# CAN0.net
KiCad netlist of a schematic drawn in Altium Designer
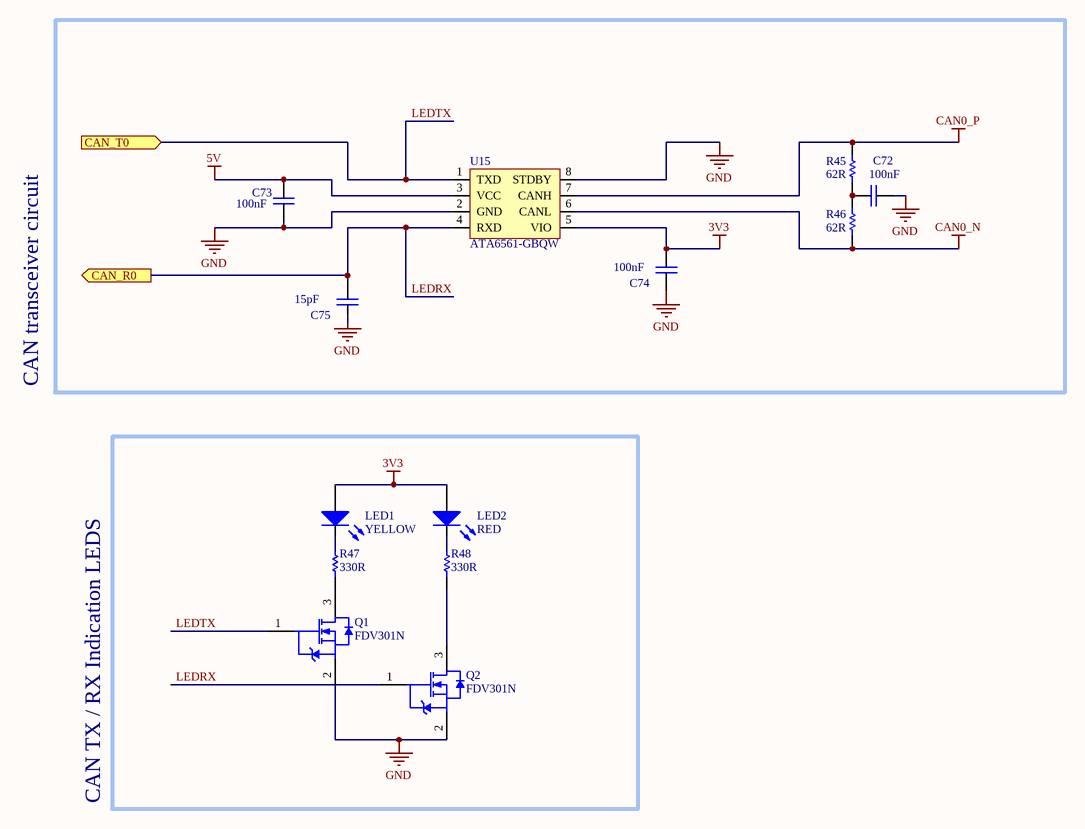
[diagram p0: CAN0.SchDoc]

(export (version "E")
  (design (tool "Eeschema 10.0.6"))
  (components
    (comp (ref "C72")
      (value "100nF")
      (footprint "C1206")
      (description "C1206")
      (fields (field (name "Comment") "C1206C106K3PACTU"))
      (libsource (lib "Passive components") (part "C1206C106K3PACTU"))
    )
    (comp (ref "C73")
      (value "100nF")
      (footprint "C1206")
      (description "C1206")
      (fields (field (name "Comment") "C1206C106K3PACTU"))
      (libsource (lib "Passive components") (part "C1206C106K3PACTU"))
    )
    (comp (ref "C74")
      (value "100nF")
      (footprint "C1206")
      (description "C1206")
      (fields (field (name "Comment") "C1206C106K3PACTU"))
      (libsource (lib "Passive components") (part "C1206C106K3PACTU"))
    )
    (comp (ref "C75")
      (value "15pF")
      (footprint "C1206")
      (description "C1206")
      (fields (field (name "Comment") "C1206C106K3PACTU"))
      (libsource (lib "Passive components") (part "C1206C106K3PACTU"))
    )
    (comp (ref "LED1")
      (value "YELLOW")
      (footprint "0603_A")
      (description "SMD mono-color Chip LED, WL-SMCW, Red")
      (fields (field (name "MANUFACTURER") "Wuerth Elektronik") (field (name "PARTNUMBER") "150060RS75000"))
      (libsource (lib "Altium Content Vault") (part "WE-LED_K1A2-2"))
    )
    (comp (ref "LED2")
      (value "RED")
      (footprint "0603_A")
      (description "SMD mono-color Chip LED, WL-SMCW, Red")
      (fields (field (name "MANUFACTURER") "Wuerth Elektronik") (field (name "PARTNUMBER") "150060RS75000"))
      (libsource (lib "Altium Content Vault") (part "WE-LED_K1A2-2"))
    )
    (comp (ref "Q1")
      (value "FDV301N")
      (footprint "FAIR-SOT23-3_V")
      (description "Digital FET, N-Channel, 0.35 W, 25 V, -55 to 150 degC, 3-Pin SOT23, RoHS, Tape and Reel")
      (fields (field (name "MANUFACTURER") "Fairchild"))
      (libsource (lib "Altium Content Vault") (part "NEMOS-GSD-3_D"))
    )
    (comp (ref "Q2")
      (value "FDV301N")
      (footprint "FAIR-SOT23-3_V")
      (description "Digital FET, N-Channel, 0.35 W, 25 V, -55 to 150 degC, 3-Pin SOT23, RoHS, Tape and Reel")
      (fields (field (name "MANUFACTURER") "Fairchild"))
      (libsource (lib "Altium Content Vault") (part "NEMOS-GSD-3_D"))
    )
    (comp (ref "R45")
      (value "62R")
      (footprint "RESC0603(1608)_L")
      (description "330R 0.1W 5% 0603 (1608 Metric)  SMD")
      (fields (field (name "TOLERANCE") "5 %") (field (name "POWER") "0.1 W"))
      (libsource (lib "Altium Content Vault") (part "RES"))
    )
    (comp (ref "R46")
      (value "62R")
      (footprint "RESC0603(1608)_L")
      (description "330R 0.1W 5% 0603 (1608 Metric)  SMD")
      (fields (field (name "TOLERANCE") "5 %") (field (name "POWER") "0.1 W"))
      (libsource (lib "Altium Content Vault") (part "RES"))
    )
    (comp (ref "R47")
      (value "330R")
      (footprint "RESC0603(1608)_L")
      (description "330R 0.1W 5% 0603 (1608 Metric)  SMD")
      (fields (field (name "TOLERANCE") "5 %") (field (name "POWER") "0.1 W"))
      (libsource (lib "Altium Content Vault") (part "RES"))
    )
    (comp (ref "R48")
      (value "330R")
      (footprint "RESC0603(1608)_L")
      (description "330R 0.1W 5% 0603 (1608 Metric)  SMD")
      (fields (field (name "TOLERANCE") "5 %") (field (name "POWER") "0.1 W"))
      (libsource (lib "Altium Content Vault") (part "RES"))
    )
    (comp (ref "U15")
      (value "ATA6561-GBQW")
      (footprint "LME49721MA/NOPB")
      (libsource (lib "IC") (part "ATA6561-GBQW"))
    )
  )
  (nets
    (net (code "1") (name "/LEDRX") (class "Default")
      (node (ref "C75") (pin "2") (pinfunction "2_2") (pintype "passive"))
      (node (ref "Q2") (pin "1") (pinfunction "G_1") (pintype "passive"))
      (node (ref "U15") (pin "4") (pinfunction "RXD_4") (pintype "passive"))
    )
    (net (code "2") (name "/LEDTX") (class "Default")
      (node (ref "Q1") (pin "1") (pinfunction "G_1") (pintype "passive"))
      (node (ref "U15") (pin "1") (pinfunction "TXD_1") (pintype "passive"))
    )
    (net (code "3") (name "3V3") (class "Default")
      (node (ref "C74") (pin "2") (pinfunction "2_2") (pintype "passive"))
      (node (ref "LED1") (pin "2") (pinfunction "A_2") (pintype "passive"))
      (node (ref "LED2") (pin "2") (pinfunction "A_2") (pintype "passive"))
      (node (ref "U15") (pin "5") (pinfunction "VIO_5") (pintype "passive"))
    )
    (net (code "4") (name "5V") (class "Default")
      (node (ref "C73") (pin "2") (pinfunction "2_2") (pintype "passive"))
      (node (ref "U15") (pin "3") (pinfunction "VCC_3") (pintype "passive"))
    )
    (net (code "5") (name "CAN0_N") (class "Default")
      (node (ref "R46") (pin "2") (pinfunction "2_2") (pintype "passive"))
      (node (ref "U15") (pin "6") (pinfunction "CANL_6") (pintype "passive"))
    )
    (net (code "6") (name "CAN0_P") (class "Default")
      (node (ref "R45") (pin "1") (pinfunction "1_1") (pintype "passive"))
      (node (ref "U15") (pin "7") (pinfunction "CANH_7") (pintype "passive"))
    )
    (net (code "7") (name "GND") (class "Default")
      (node (ref "C72") (pin "1") (pinfunction "1_1") (pintype "passive"))
      (node (ref "C73") (pin "1") (pinfunction "1_1") (pintype "passive"))
      (node (ref "C74") (pin "1") (pinfunction "1_1") (pintype "passive"))
      (node (ref "C75") (pin "1") (pinfunction "1_1") (pintype "passive"))
      (node (ref "Q1") (pin "2") (pinfunction "S_2") (pintype "passive"))
      (node (ref "Q2") (pin "2") (pinfunction "S_2") (pintype "passive"))
      (node (ref "U15") (pin "2") (pinfunction "GND_2") (pintype "passive"))
      (node (ref "U15") (pin "8") (pinfunction "STDBY_8") (pintype "passive"))
    )
    (net (code "8") (name "Net-(C72-Pad2)") (class "Default")
      (node (ref "C72") (pin "2") (pinfunction "2_2") (pintype "passive"))
      (node (ref "R45") (pin "2") (pinfunction "2_2") (pintype "passive"))
      (node (ref "R46") (pin "1") (pinfunction "1_1") (pintype "passive"))
    )
    (net (code "9") (name "Net-(LED1-K)") (class "Default")
      (node (ref "LED1") (pin "1") (pinfunction "K_1") (pintype "passive"))
      (node (ref "R47") (pin "1") (pinfunction "1_1") (pintype "passive"))
    )
    (net (code "10") (name "Net-(LED2-K)") (class "Default")
      (node (ref "LED2") (pin "1") (pinfunction "K_1") (pintype "passive"))
      (node (ref "R48") (pin "1") (pinfunction "1_1") (pintype "passive"))
    )
    (net (code "11") (name "Net-(Q1-D)") (class "Default")
      (node (ref "Q1") (pin "3") (pinfunction "D_3") (pintype "passive"))
      (node (ref "R47") (pin "2") (pinfunction "2_2") (pintype "passive"))
    )
    (net (code "12") (name "Net-(Q2-D)") (class "Default")
      (node (ref "Q2") (pin "3") (pinfunction "D_3") (pintype "passive"))
      (node (ref "R48") (pin "2") (pinfunction "2_2") (pintype "passive"))
    )
  )
)
